# CAN.net
KiCad netlist of a schematic drawn in Altium Designer
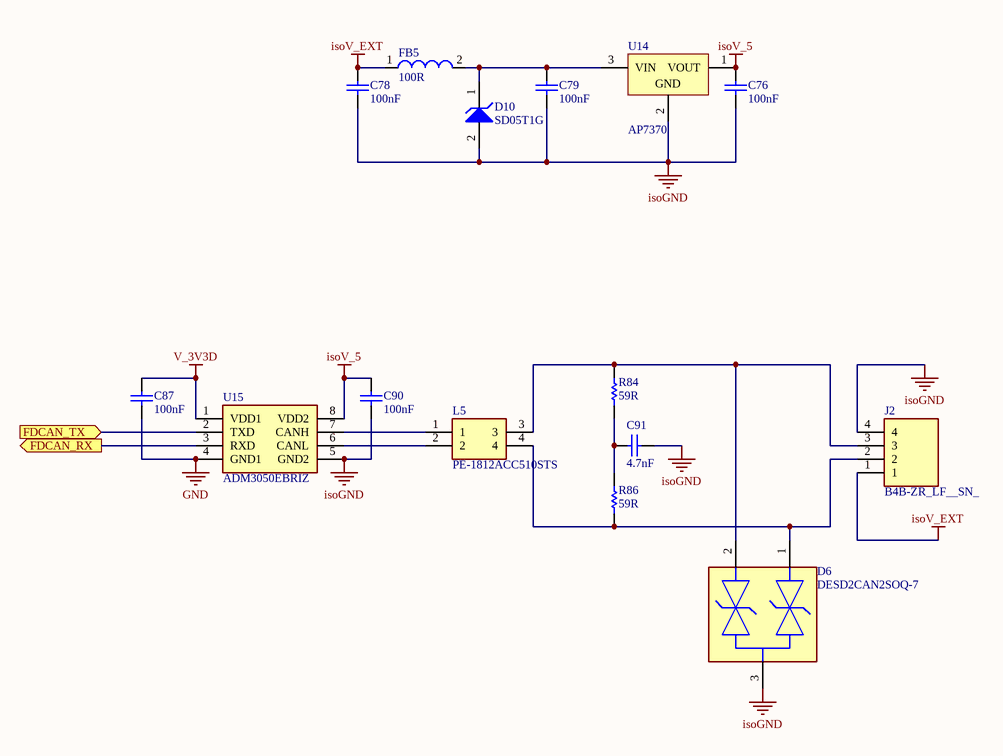
[diagram p0: CAN.SchDoc]

(export (version "E")
  (design (tool "Eeschema 10.0.6"))
  (components
    (comp (ref "C76")
      (value "100nF")
      (footprint "CAPC1608X90X35NL10T15")
      (description "X7R 100nF ±10% 50V 0603 Multilayer Ceramic Capacitors MLCC - SMD/SMT ROHS")
      (fields (field (name "PART NUMBER") "GCM188R72A104KA64D") (field (name "MANUFACTURER") "Murata"))
      (libsource (lib "DCDC") (part "CAP"))
    )
    (comp (ref "C78")
      (value "100nF")
      (footprint "CAPC1608X90X35NL10T15")
      (description "X7R 100nF ±10% 50V 0603 Multilayer Ceramic Capacitors MLCC - SMD/SMT ROHS")
      (fields (field (name "PART NUMBER") "GCM188R72A104KA64D") (field (name "MANUFACTURER") "Murata"))
      (libsource (lib "DCDC") (part "CAP"))
    )
    (comp (ref "C79")
      (value "100nF")
      (footprint "CAPC1608X90X35NL10T15")
      (description "X7R 100nF ±10% 50V 0603 Multilayer Ceramic Capacitors MLCC - SMD/SMT ROHS")
      (fields (field (name "PART NUMBER") "GCM188R72A104KA64D") (field (name "MANUFACTURER") "Murata"))
      (libsource (lib "DCDC") (part "CAP"))
    )
    (comp (ref "C87")
      (value "100nF")
      (footprint "CAPC1608X90X35NL10T15")
      (description "X7R 100nF ±10% 50V 0603 Multilayer Ceramic Capacitors MLCC - SMD/SMT ROHS")
      (fields (field (name "PART NUMBER") "GCM188R72A104KA64D") (field (name "MANUFACTURER") "Murata"))
      (libsource (lib "DCDC") (part "CAP"))
    )
    (comp (ref "C90")
      (value "100nF")
      (footprint "CAPC1608X90X35NL10T15")
      (description "X7R 100nF ±10% 50V 0603 Multilayer Ceramic Capacitors MLCC - SMD/SMT ROHS")
      (fields (field (name "PART NUMBER") "GCM188R72A104KA64D") (field (name "MANUFACTURER") "Murata"))
      (libsource (lib "DCDC") (part "CAP"))
    )
    (comp (ref "C91")
      (value "4.7nF")
      (footprint "CAPC1608X90X35ML10T15")
      (description "X7R ±10% 4.7nF 50V 0603 Multilayer Ceramic Capacitors MLCC - SMD/SMT ROHS")
      (fields (field (name "PART NUMBER") "GRM188R71H472KA01D") (field (name "MANUFACTURER") "Murata"))
      (libsource (lib "Altium Content Vault") (part "CAP"))
    )
    (comp (ref "D6")
      (value "DESD2CAN2SOQ-7")
      (footprint "FP-SOT23-MFG")
      (description "TVS DIODE 24V 41V SOT23")
      (fields
        (field (name "OCTOPART") "https://octopart.com/desd2can2soq-7-diodes+inc.-53081564")
        (field (name "MANUFACTURER") "Diodes Inc.")
      )
      (libsource (lib "Altium Content Vault") (part "763a38cec178d78307674f83e5f67f4"))
    )
    (comp (ref "D10")
      (value "SD05T1G")
      (footprint "ONSC-SOD-323-2-477-02_G_V")
      (description "Transient Voltage Suppressor Diode, for ESD Protection, 2-Pin SOD-323, Pb-Free, Tape and Reel")
      (fields (field (name "MANUFACTURER") "On Semiconductor"))
      (libsource (lib "Altium Content Vault") (part "ONSC-K1A2-2"))
    )
    (comp (ref "FB5")
      (value "100R")
      (footprint "SMD-0603")
      (description "SMD EMI Suppression Ferrite Bead WE-CBF, Z = 1500 Ohm")
      (libsource (lib "Altium Content Vault") (part "PAS-IND-INDUCTOR-2"))
    )
    (comp (ref "J2")
      (value "B4B-ZR_LF__SN_")
      (footprint "SamacSys:SHDR4W50P0X150_1X4_750X350X450P")
      (description "Connector")
      (fields (field (name "MANUFACTURER_PART_NUMBER") "B4B-ZR(LF)(SN)"))
      (libsource (lib "*") (part "B4B-ZR_LF__SN_"))
    )
    (comp (ref "L5")
      (value "PE-1812ACC510STS")
      (footprint "SamacSys:PE1812ACC510STS")
      (description "Inductor")
      (fields (field (name "MOUSER PART NUMBER") "673-PE-1812ACC510STS"))
      (libsource (lib "*") (part "PE-1812ACC510STS"))
    )
    (comp (ref "R84")
      (value "59R")
      (footprint "RESC1608X55X30ML15T15")
      (fields
        (field (name "MANUFACTURER") "Panasonic")
        (field (name "PART NUMBER") "ERJ-3EKF59R0V")
        (field (name "TOLERANCE") "1%")
      )
      (libsource (lib "Altium Content Vault") (part "RES"))
    )
    (comp (ref "R86")
      (value "59R")
      (footprint "RESC1608X55X30ML15T15")
      (fields
        (field (name "MANUFACTURER") "Panasonic")
        (field (name "PART NUMBER") "ERJ-3EKF59R0V")
        (field (name "TOLERANCE") "1%")
      )
      (libsource (lib "Altium Content Vault") (part "RES"))
    )
    (comp (ref "U14")
      (value "AP7370")
      (footprint "SOT-89_L")
      (libsource (lib "Altium Content Vault") (part "PM-REG-7805-SIL3"))
    )
    (comp (ref "U15")
      (value "ADM3050EBRIZ")
      (footprint "SamacSys:SOIC127P1031X265-8N")
      (description "Integrated Circuit")
      (fields (field (name "MOUSER PART NUMBER") "584-ADM3050EBRIZ"))
      (libsource (lib "*") (part "ADM3050EBRIZ"))
    )
  )
  (nets
    (net (code "1") (name "/FDCAN_RX") (class "Default")
      (node (ref "U15") (pin "3") (pinfunction "RXD_3") (pintype "passive"))
    )
    (net (code "2") (name "/FDCAN_TX") (class "Default")
      (node (ref "U15") (pin "2") (pinfunction "TXD_2") (pintype "passive"))
    )
    (net (code "3") (name "GND") (class "Default")
      (node (ref "C87") (pin "1") (pinfunction "1_1") (pintype "passive"))
      (node (ref "U15") (pin "4") (pinfunction "GND1_4") (pintype "passive"))
    )
    (net (code "4") (name "Net-(C91-Pad1)") (class "Default")
      (node (ref "C91") (pin "1") (pinfunction "1_1") (pintype "passive"))
      (node (ref "R84") (pin "1") (pinfunction "1_1") (pintype "passive"))
      (node (ref "R86") (pin "2") (pinfunction "2_2") (pintype "passive"))
    )
    (net (code "5") (name "Net-(D6-Pad1)") (class "Default")
      (node (ref "D6") (pin "1") (pinfunction "1_1") (pintype "passive"))
      (node (ref "J2") (pin "2") (pinfunction "2_2") (pintype "passive"))
      (node (ref "L5") (pin "4") (pinfunction "4_4") (pintype "passive"))
      (node (ref "R86") (pin "1") (pinfunction "1_1") (pintype "passive"))
    )
    (net (code "6") (name "Net-(D6-Pad2)") (class "Default")
      (node (ref "D6") (pin "2") (pinfunction "2_2") (pintype "passive"))
      (node (ref "J2") (pin "3") (pinfunction "3_3") (pintype "passive"))
      (node (ref "L5") (pin "3") (pinfunction "3_3") (pintype "passive"))
      (node (ref "R84") (pin "2") (pinfunction "2_2") (pintype "passive"))
    )
    (net (code "7") (name "Net-(D10-K)") (class "Default")
      (node (ref "C79") (pin "2") (pinfunction "2_2") (pintype "passive"))
      (node (ref "D10") (pin "1") (pinfunction "K_1") (pintype "passive"))
      (node (ref "FB5") (pin "2") (pinfunction "2_2") (pintype "passive"))
      (node (ref "U14") (pin "3") (pinfunction "VIN_3") (pintype "power_in"))
    )
    (net (code "8") (name "Net-(U15-CANH)") (class "Default")
      (node (ref "L5") (pin "1") (pinfunction "1_1") (pintype "passive"))
      (node (ref "U15") (pin "7") (pinfunction "CANH_7") (pintype "passive"))
    )
    (net (code "9") (name "Net-(U15-CANL)") (class "Default")
      (node (ref "L5") (pin "2") (pinfunction "2_2") (pintype "passive"))
      (node (ref "U15") (pin "6") (pinfunction "CANL_6") (pintype "passive"))
    )
    (net (code "10") (name "V_3V3D") (class "Default")
      (node (ref "C87") (pin "2") (pinfunction "2_2") (pintype "passive"))
      (node (ref "U15") (pin "1") (pinfunction "VDD1_1") (pintype "passive"))
    )
    (net (code "11") (name "isoGND") (class "Default")
      (node (ref "C76") (pin "1") (pinfunction "1_1") (pintype "passive"))
      (node (ref "C78") (pin "1") (pinfunction "1_1") (pintype "passive"))
      (node (ref "C79") (pin "1") (pinfunction "1_1") (pintype "passive"))
      (node (ref "C90") (pin "1") (pinfunction "1_1") (pintype "passive"))
      (node (ref "C91") (pin "2") (pinfunction "2_2") (pintype "passive"))
      (node (ref "D10") (pin "2") (pinfunction "A_2") (pintype "passive"))
      (node (ref "D6") (pin "3") (pinfunction "3_3") (pintype "passive"))
      (node (ref "J2") (pin "4") (pinfunction "4_4") (pintype "passive"))
      (node (ref "U14") (pin "2") (pinfunction "GND_2") (pintype "power_in"))
      (node (ref "U15") (pin "5") (pinfunction "GND2_5") (pintype "passive"))
    )
    (net (code "12") (name "isoV_5") (class "Default")
      (node (ref "C76") (pin "2") (pinfunction "2_2") (pintype "passive"))
      (node (ref "C90") (pin "2") (pinfunction "2_2") (pintype "passive"))
      (node (ref "U14") (pin "1") (pinfunction "VOUT_1") (pintype "power_in"))
      (node (ref "U15") (pin "8") (pinfunction "VDD2_8") (pintype "passive"))
    )
    (net (code "13") (name "isoV_EXT") (class "Default")
      (node (ref "C78") (pin "2") (pinfunction "2_2") (pintype "passive"))
      (node (ref "FB5") (pin "1") (pinfunction "1_1") (pintype "passive"))
      (node (ref "J2") (pin "1") (pinfunction "1_1") (pintype "passive"))
    )
  )
)
